# main.net
KiCad netlist of a schematic drawn in EAGLE
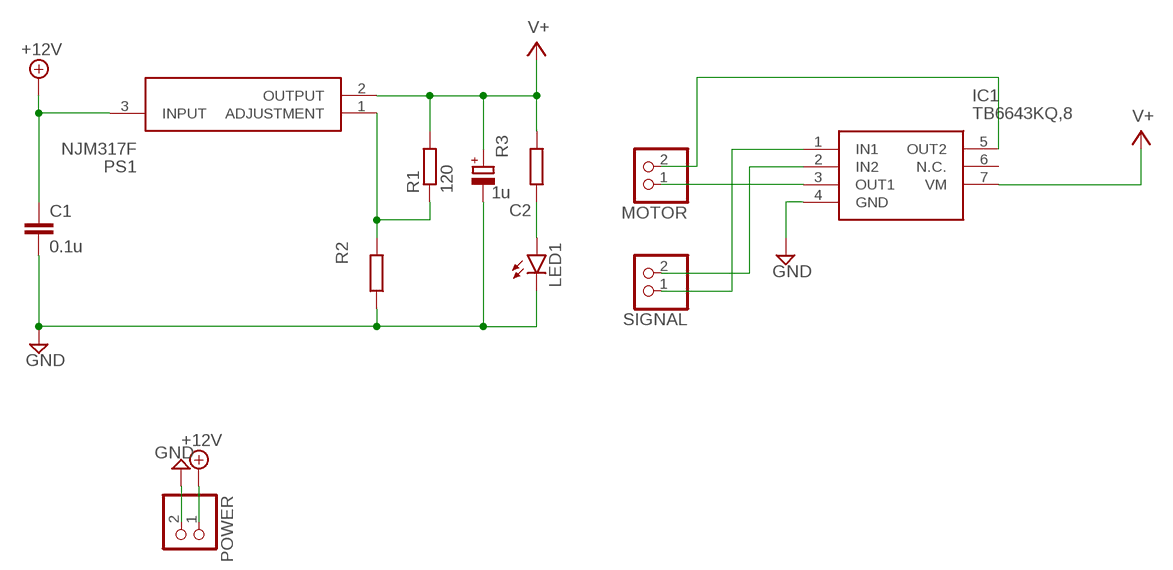
[diagram p0: schematic, sheet 1]

(export (version "E")
  (design (tool "Eeschema 10.0.6"))
  (components
    (comp (ref "C1")
      (value "0.1u")
      (footprint "eagle-import:C050-024X044")
      (libsource (lib "eagle-import") (part "C-EU050-024X044"))
    )
    (comp (ref "C2")
      (value "1u")
      (footprint "eagle-import:E2,5-7")
      (libsource (lib "eagle-import") (part "CPOL-EUE2.5-7"))
    )
    (comp (ref "IC1")
      (value "TB6643KQ,8")
      (footprint "eagle-import:HSIP7-P-2.54A")
      (fields (field (name "MOUSER_PART_NUMBER") "757-TB6643KQ8"))
      (libsource (lib "eagle-import") (part "TB6643KQ,8"))
    )
    (comp (ref "LED1")
      (value "LED5MM")
      (footprint "eagle-import:LED5MM")
      (libsource (lib "eagle-import") (part "LED5MM"))
    )
    (comp (ref "MOTOR")
      (value "PINHD-1X2")
      (footprint "eagle-import:1X02")
      (libsource (lib "eagle-import") (part "PINHD-1X2"))
    )
    (comp (ref "POWER")
      (value "PINHD-1X2")
      (footprint "eagle-import:1X02")
      (libsource (lib "eagle-import") (part "PINHD-1X2"))
    )
    (comp (ref "PS1")
      (value "NJM317F")
      (footprint "eagle-import:TO254P500X1000X2170-3P")
      (fields (field (name "MOUSER_PART_NUMBER") "513-NJM317F"))
      (libsource (lib "eagle-import") (part "NJM317F"))
    )
    (comp (ref "R1")
      (value "120")
      (footprint "eagle-import:0207_10")
      (libsource (lib "eagle-import") (part "R-EU_0207/10"))
    )
    (comp (ref "R2")
      (value "R-EU_0207/10")
      (footprint "eagle-import:0207_10")
      (libsource (lib "eagle-import") (part "R-EU_0207/10"))
    )
    (comp (ref "R3")
      (value "R-EU_0207/10")
      (footprint "eagle-import:0207_10")
      (libsource (lib "eagle-import") (part "R-EU_0207/10"))
    )
    (comp (ref "SIGNAL")
      (value "PINHD-1X2")
      (footprint "eagle-import:1X02")
      (libsource (lib "eagle-import") (part "PINHD-1X2"))
    )
  )
  (nets
    (net (code "1") (name "+12V") (class "Default")
      (node (ref "C1") (pin "1") (pinfunction "1_1") (pintype "passive"))
      (node (ref "POWER") (pin "1") (pinfunction "1_1") (pintype "passive"))
      (node (ref "PS1") (pin "3") (pinfunction "INPUT_3") (pintype "bidirectional"))
    )
    (net (code "2") (name "GND") (class "Default")
      (node (ref "C1") (pin "2") (pinfunction "2_2") (pintype "passive"))
      (node (ref "C2") (pin "-") (pinfunction "-_-") (pintype "passive"))
      (node (ref "IC1") (pin "4") (pinfunction "GND_4") (pintype "bidirectional"))
      (node (ref "LED1") (pin "K") (pinfunction "C_K") (pintype "passive"))
      (node (ref "POWER") (pin "2") (pinfunction "2_2") (pintype "passive"))
      (node (ref "R2") (pin "1") (pinfunction "1_1") (pintype "passive"))
    )
    (net (code "3") (name "Net-(IC1-IN1)") (class "Default")
      (node (ref "IC1") (pin "1") (pinfunction "IN1_1") (pintype "bidirectional"))
      (node (ref "SIGNAL") (pin "1") (pinfunction "1_1") (pintype "passive"))
    )
    (net (code "4") (name "Net-(IC1-IN2)") (class "Default")
      (node (ref "IC1") (pin "2") (pinfunction "IN2_2") (pintype "bidirectional"))
      (node (ref "SIGNAL") (pin "2") (pinfunction "2_2") (pintype "passive"))
    )
    (net (code "5") (name "Net-(IC1-OUT1)") (class "Default")
      (node (ref "IC1") (pin "3") (pinfunction "OUT1_3") (pintype "bidirectional"))
      (node (ref "MOTOR") (pin "1") (pinfunction "1_1") (pintype "passive"))
    )
    (net (code "6") (name "Net-(IC1-OUT2)") (class "Default")
      (node (ref "IC1") (pin "5") (pinfunction "OUT2_5") (pintype "bidirectional"))
      (node (ref "MOTOR") (pin "2") (pinfunction "2_2") (pintype "passive"))
    )
    (net (code "7") (name "Net-(LED1-PadA)") (class "Default")
      (node (ref "LED1") (pin "A") (pinfunction "A_A") (pintype "passive"))
      (node (ref "R3") (pin "1") (pinfunction "1_1") (pintype "passive"))
    )
    (net (code "8") (name "Net-(PS1-ADJUSTMENT)") (class "Default")
      (node (ref "PS1") (pin "1") (pinfunction "ADJUSTMENT_1") (pintype "bidirectional"))
      (node (ref "R1") (pin "1") (pinfunction "1_1") (pintype "passive"))
      (node (ref "R2") (pin "2") (pinfunction "2_2") (pintype "passive"))
    )
    (net (code "9") (name "V+") (class "Default")
      (node (ref "C2") (pin "+") (pinfunction "+_+") (pintype "passive"))
      (node (ref "IC1") (pin "7") (pinfunction "VM_7") (pintype "bidirectional"))
      (node (ref "PS1") (pin "2") (pinfunction "OUTPUT_2") (pintype "bidirectional"))
      (node (ref "R1") (pin "2") (pinfunction "2_2") (pintype "passive"))
      (node (ref "R3") (pin "2") (pinfunction "2_2") (pintype "passive"))
    )
    (net (code "10") (name "unconnected-(IC1-N.C.-Pad6)") (class "Default")
      (node (ref "IC1") (pin "6") (pinfunction "N.C._6") (pintype "no_connect"))
    )
  )
)
